# schematic.net
KiCad netlist of a schematic drawn in EAGLE
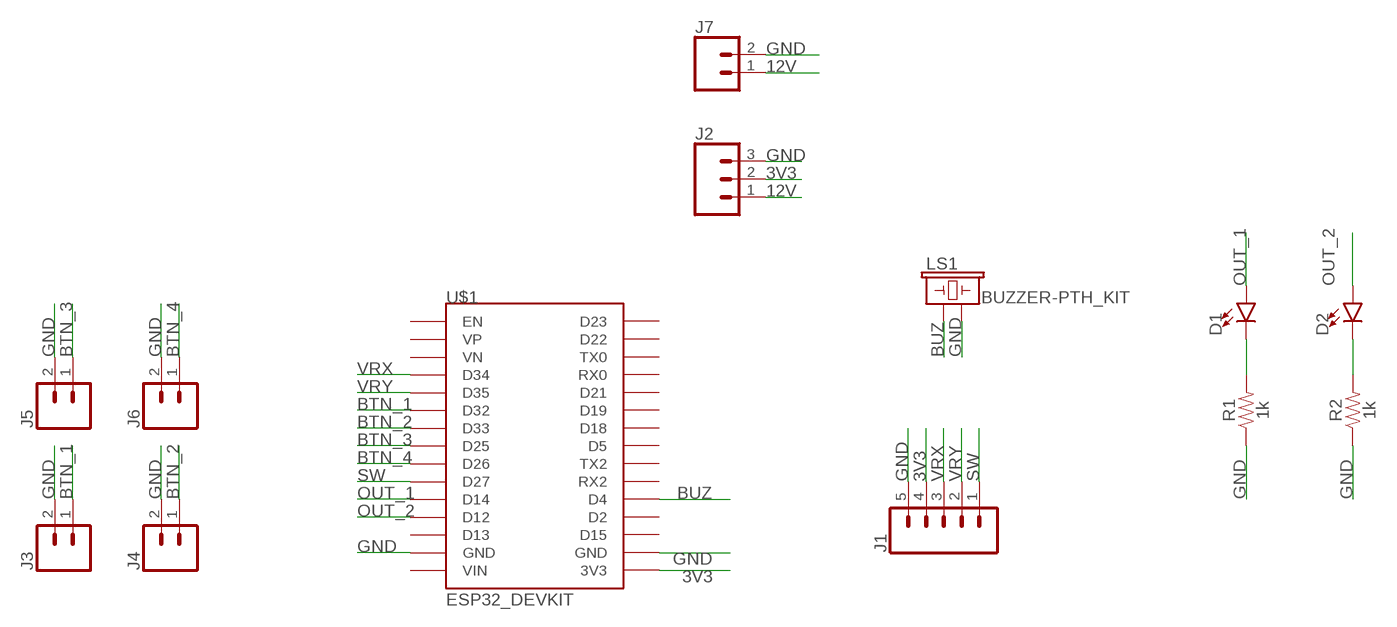
[diagram p0: schematic, sheet 1]

(export (version "E")
  (design (tool "Eeschema 10.0.6"))
  (components
    (comp (ref "D1")
      (value "LED5MM")
      (footprint "eagle-import:LED_5MM")
      (libsource (lib "eagle-import") (part "LED5MM"))
    )
    (comp (ref "D2")
      (value "LED5MM")
      (footprint "eagle-import:LED_5MM")
      (libsource (lib "eagle-import") (part "LED5MM"))
    )
    (comp (ref "J1")
      (value "CONN_05LOCK")
      (footprint "eagle-import:1X05_LOCK")
      (libsource (lib "eagle-import") (part "CONN_05LOCK"))
    )
    (comp (ref "J2")
      (value "CONN_03SCREW")
      (footprint "eagle-import:SCREWTERMINAL-3.5MM-3")
      (libsource (lib "eagle-import") (part "CONN_03SCREW"))
    )
    (comp (ref "J3")
      (value "CONN_02")
      (footprint "eagle-import:1X02")
      (libsource (lib "eagle-import") (part "CONN_02"))
    )
    (comp (ref "J4")
      (value "CONN_02")
      (footprint "eagle-import:1X02")
      (libsource (lib "eagle-import") (part "CONN_02"))
    )
    (comp (ref "J5")
      (value "CONN_02")
      (footprint "eagle-import:1X02")
      (libsource (lib "eagle-import") (part "CONN_02"))
    )
    (comp (ref "J6")
      (value "CONN_02")
      (footprint "eagle-import:1X02")
      (libsource (lib "eagle-import") (part "CONN_02"))
    )
    (comp (ref "J7")
      (value "CONN_02LOCK")
      (footprint "eagle-import:1X02_LOCK")
      (libsource (lib "eagle-import") (part "CONN_02LOCK"))
    )
    (comp (ref "LS1")
      (value "BUZZER-PTH_KIT")
      (footprint "eagle-import:BUZZER-12MM-KIT")
      (libsource (lib "eagle-import") (part "BUZZER-PTH_KIT"))
    )
    (comp (ref "R1")
      (value "1k")
      (footprint "eagle-import:AXIAL-0.3")
      (libsource (lib "eagle-import") (part "1KOHM-HORIZ-1/4W-5%"))
    )
    (comp (ref "R2")
      (value "1k")
      (footprint "eagle-import:AXIAL-0.3")
      (libsource (lib "eagle-import") (part "1KOHM-HORIZ-1/4W-1%"))
    )
    (comp (ref "U$1")
      (value "ESP32_DEVKIT")
      (footprint "eagle-import:ESP32_DEVKIT")
      (libsource (lib "eagle-import") (part "ESP32_DEVKIT"))
    )
  )
  (nets
    (net (code "1") (name "/3V3") (class "Default")
      (node (ref "J1") (pin "4") (pinfunction "4_4") (pintype "passive"))
      (node (ref "J2") (pin "2") (pinfunction "2_2") (pintype "passive"))
      (node (ref "U$1") (pin "3V3") (pinfunction "3V3_3V3") (pintype "bidirectional"))
    )
    (net (code "2") (name "/12V") (class "Default")
      (node (ref "J2") (pin "1") (pinfunction "1_1") (pintype "passive"))
      (node (ref "J7") (pin "1") (pinfunction "1_1") (pintype "passive"))
    )
    (net (code "3") (name "/BTN_1") (class "Default")
      (node (ref "J3") (pin "1") (pinfunction "1_1") (pintype "passive"))
      (node (ref "U$1") (pin "D32") (pinfunction "D32_D32") (pintype "bidirectional"))
    )
    (net (code "4") (name "/BTN_2") (class "Default")
      (node (ref "J4") (pin "1") (pinfunction "1_1") (pintype "passive"))
      (node (ref "U$1") (pin "D33") (pinfunction "D33_D33") (pintype "bidirectional"))
    )
    (net (code "5") (name "/BTN_3") (class "Default")
      (node (ref "J5") (pin "1") (pinfunction "1_1") (pintype "passive"))
      (node (ref "U$1") (pin "D25") (pinfunction "D25_D25") (pintype "bidirectional"))
    )
    (net (code "6") (name "/BTN_4") (class "Default")
      (node (ref "J6") (pin "1") (pinfunction "1_1") (pintype "passive"))
      (node (ref "U$1") (pin "D26") (pinfunction "D26_D26") (pintype "bidirectional"))
    )
    (net (code "7") (name "/BUZ") (class "Default")
      (node (ref "LS1") (pin "+") (pinfunction "1_+") (pintype "passive"))
      (node (ref "U$1") (pin "D4") (pinfunction "D4_D4") (pintype "bidirectional"))
    )
    (net (code "8") (name "/GND") (class "Default")
      (node (ref "J1") (pin "5") (pinfunction "5_5") (pintype "passive"))
      (node (ref "J2") (pin "3") (pinfunction "3_3") (pintype "passive"))
      (node (ref "J3") (pin "2") (pinfunction "2_2") (pintype "passive"))
      (node (ref "J4") (pin "2") (pinfunction "2_2") (pintype "passive"))
      (node (ref "J5") (pin "2") (pinfunction "2_2") (pintype "passive"))
      (node (ref "J6") (pin "2") (pinfunction "2_2") (pintype "passive"))
      (node (ref "J7") (pin "2") (pinfunction "2_2") (pintype "passive"))
      (node (ref "LS1") (pin "-") (pinfunction "2_-") (pintype "passive"))
      (node (ref "R1") (pin "P$1") (pinfunction "1_P$1") (pintype "passive"))
      (node (ref "R2") (pin "P$1") (pinfunction "1_P$1") (pintype "passive"))
      (node (ref "U$1") (pin "GND@1") (pinfunction "GND_GND@1") (pintype "bidirectional"))
      (node (ref "U$1") (pin "GND@2") (pinfunction "GND_GND@2") (pintype "bidirectional"))
    )
    (net (code "9") (name "/OUT_1") (class "Default")
      (node (ref "D1") (pin "A") (pinfunction "A_A") (pintype "passive"))
      (node (ref "U$1") (pin "D14") (pinfunction "D14_D14") (pintype "bidirectional"))
    )
    (net (code "10") (name "/OUT_2") (class "Default")
      (node (ref "D2") (pin "A") (pinfunction "A_A") (pintype "passive"))
      (node (ref "U$1") (pin "D12") (pinfunction "D12_D12") (pintype "bidirectional"))
    )
    (net (code "11") (name "/SW") (class "Default")
      (node (ref "J1") (pin "1") (pinfunction "1_1") (pintype "passive"))
      (node (ref "U$1") (pin "D27") (pinfunction "D27_D27") (pintype "bidirectional"))
    )
    (net (code "12") (name "/VRX") (class "Default")
      (node (ref "J1") (pin "3") (pinfunction "3_3") (pintype "passive"))
      (node (ref "U$1") (pin "D34") (pinfunction "D34_D34") (pintype "bidirectional"))
    )
    (net (code "13") (name "/VRY") (class "Default")
      (node (ref "J1") (pin "2") (pinfunction "2_2") (pintype "passive"))
      (node (ref "U$1") (pin "D35") (pinfunction "D35_D35") (pintype "bidirectional"))
    )
    (net (code "14") (name "Net-(D1-C)") (class "Default")
      (node (ref "D1") (pin "K") (pinfunction "C_K") (pintype "passive"))
      (node (ref "R1") (pin "P$2") (pinfunction "2_P$2") (pintype "passive"))
    )
    (net (code "15") (name "Net-(D2-C)") (class "Default")
      (node (ref "D2") (pin "K") (pinfunction "C_K") (pintype "passive"))
      (node (ref "R2") (pin "P$2") (pinfunction "2_P$2") (pintype "passive"))
    )
    (net (code "16") (name "unconnected-(U$1-PadD2)") (class "Default")
      (node (ref "U$1") (pin "D2") (pinfunction "D2_D2") (pintype "bidirectional"))
    )
    (net (code "17") (name "unconnected-(U$1-PadD5)") (class "Default")
      (node (ref "U$1") (pin "D5") (pinfunction "D5_D5") (pintype "bidirectional"))
    )
    (net (code "18") (name "unconnected-(U$1-PadD13)") (class "Default")
      (node (ref "U$1") (pin "D13") (pinfunction "D13_D13") (pintype "bidirectional"))
    )
    (net (code "19") (name "unconnected-(U$1-PadD15)") (class "Default")
      (node (ref "U$1") (pin "D15") (pinfunction "D15_D15") (pintype "bidirectional"))
    )
    (net (code "20") (name "unconnected-(U$1-PadD18)") (class "Default")
      (node (ref "U$1") (pin "D18") (pinfunction "D18_D18") (pintype "bidirectional"))
    )
    (net (code "21") (name "unconnected-(U$1-PadD19)") (class "Default")
      (node (ref "U$1") (pin "D19") (pinfunction "D19_D19") (pintype "bidirectional"))
    )
    (net (code "22") (name "unconnected-(U$1-PadD21)") (class "Default")
      (node (ref "U$1") (pin "D21") (pinfunction "D21_D21") (pintype "bidirectional"))
    )
    (net (code "23") (name "unconnected-(U$1-PadD22)") (class "Default")
      (node (ref "U$1") (pin "D22") (pinfunction "D22_D22") (pintype "bidirectional"))
    )
    (net (code "24") (name "unconnected-(U$1-PadD23)") (class "Default")
      (node (ref "U$1") (pin "D23") (pinfunction "D23_D23") (pintype "bidirectional"))
    )
    (net (code "25") (name "unconnected-(U$1-PadEN)") (class "Default")
      (node (ref "U$1") (pin "EN") (pinfunction "EN_EN") (pintype "bidirectional"))
    )
    (net (code "26") (name "unconnected-(U$1-PadRX0)") (class "Default")
      (node (ref "U$1") (pin "RX0") (pinfunction "RX0_RX0") (pintype "bidirectional"))
    )
    (net (code "27") (name "unconnected-(U$1-PadRX2)") (class "Default")
      (node (ref "U$1") (pin "RX2") (pinfunction "RX2_RX2") (pintype "bidirectional"))
    )
    (net (code "28") (name "unconnected-(U$1-PadTX0)") (class "Default")
      (node (ref "U$1") (pin "TX0") (pinfunction "TX0_TX0") (pintype "bidirectional"))
    )
    (net (code "29") (name "unconnected-(U$1-PadTX2)") (class "Default")
      (node (ref "U$1") (pin "TX2") (pinfunction "TX2_TX2") (pintype "bidirectional"))
    )
    (net (code "30") (name "unconnected-(U$1-PadVIN)") (class "Default")
      (node (ref "U$1") (pin "VIN") (pinfunction "VIN_VIN") (pintype "bidirectional"))
    )
    (net (code "31") (name "unconnected-(U$1-PadVN)") (class "Default")
      (node (ref "U$1") (pin "VN") (pinfunction "VN_VN") (pintype "bidirectional"))
    )
    (net (code "32") (name "unconnected-(U$1-PadVP)") (class "Default")
      (node (ref "U$1") (pin "VP") (pinfunction "VP_VP") (pintype "bidirectional"))
    )
  )
)
